# Mailbox_Notifier_2_1.net
KiCad netlist of a schematic drawn in EAGLE
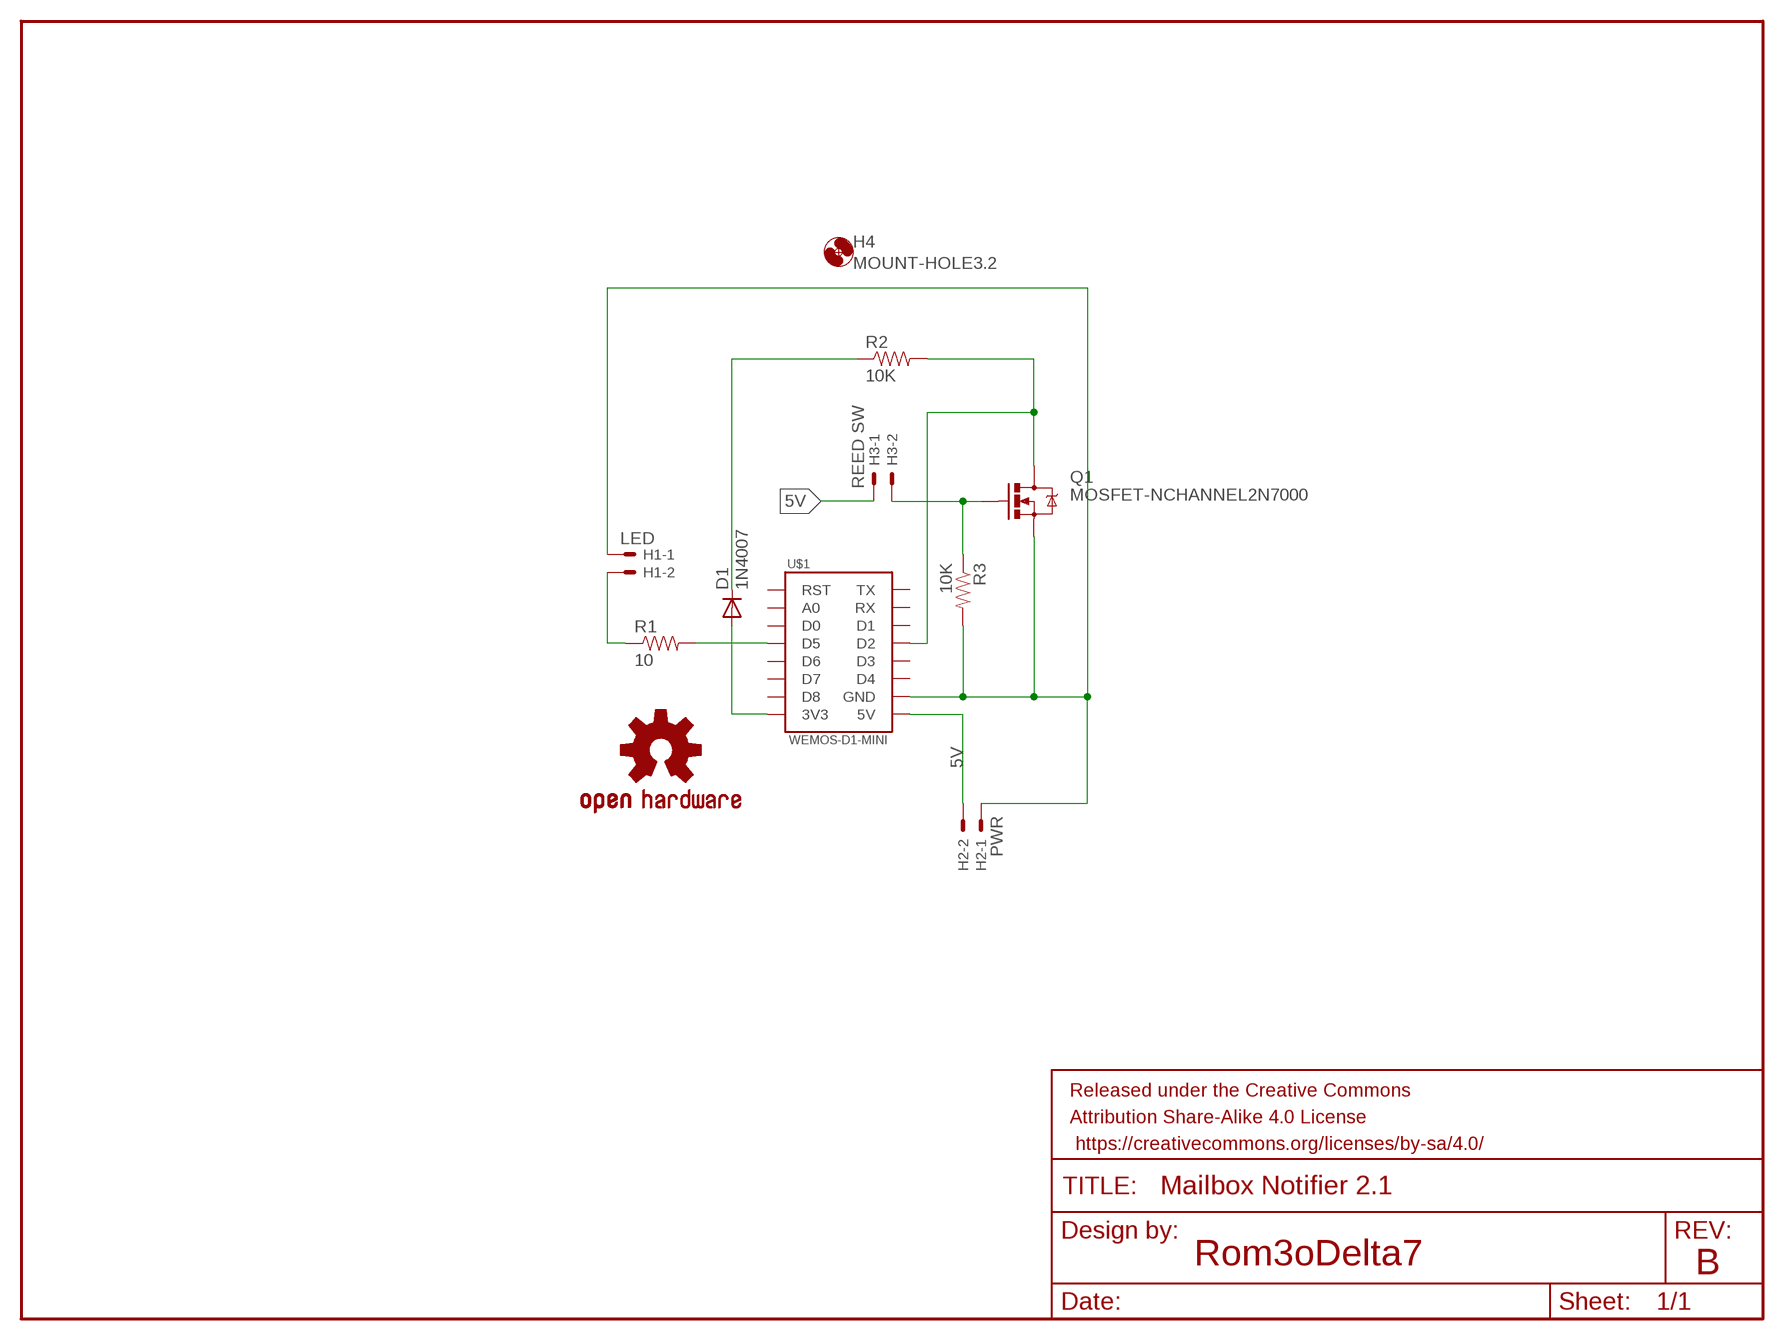
[diagram p0: schematic, sheet 1]

(export (version "E")
  (design (tool "Eeschema 10.0.6"))
  (components
    (comp (ref "D1")
      (value "1N4007")
      (footprint "eagle-import:DO41-10")
      (libsource (lib "eagle-import") (part "1N4004"))
    )
    (comp (ref "FRAME1")
      (value "FRAME-LETTER")
      (footprint "eagle-import:CREATIVE_COMMONS")
      (libsource (lib "eagle-import") (part "FRAME-LETTER"))
    )
    (comp (ref "H1")
      (value "LED")
      (footprint "eagle-import:22-23-2021")
      (fields (field (name "MF") "MOLEX") (field (name "MPN") "22-23-2021"))
      (libsource (lib "eagle-import") (part "22-23-2021"))
    )
    (comp (ref "H2")
      (value "PWR")
      (footprint "eagle-import:22-23-2021")
      (fields (field (name "MF") "MOLEX") (field (name "MPN") "22-23-2021"))
      (libsource (lib "eagle-import") (part "22-23-2021"))
    )
    (comp (ref "H3")
      (value "REED SW")
      (footprint "eagle-import:22-23-2021")
      (fields (field (name "MF") "MOLEX") (field (name "MPN") "22-23-2021"))
      (libsource (lib "eagle-import") (part "22-23-2021"))
    )
    (comp (ref "H4")
      (value "MOUNT-HOLE3.2")
      (footprint "eagle-import:3,2")
      (libsource (lib "eagle-import") (part "MOUNT-HOLE3.2"))
    )
    (comp (ref "LOGO1")
      (value "OSHW-LOGOMINI")
      (footprint "eagle-import:OSHW-LOGO-MINI")
      (libsource (lib "eagle-import") (part "OSHW-LOGOMINI"))
    )
    (comp (ref "Q1")
      (value "MOSFET-NCHANNEL2N7000")
      (footprint "eagle-import:TO-92")
      (libsource (lib "eagle-import") (part "MOSFET-NCHANNEL2N7000"))
    )
    (comp (ref "R1")
      (value "10")
      (footprint "eagle-import:AXIAL-0.5")
      (libsource (lib "eagle-import") (part "RESISTORPTH-1/2W"))
    )
    (comp (ref "R2")
      (value "10K")
      (footprint "eagle-import:AXIAL-0.4")
      (libsource (lib "eagle-import") (part "RESISTORPTH-1/4W"))
    )
    (comp (ref "R3")
      (value "10K")
      (footprint "eagle-import:AXIAL-0.4")
      (libsource (lib "eagle-import") (part "RESISTORPTH-1/4W"))
    )
    (comp (ref "U$1")
      (value "WEMOS-D1-MINI")
      (footprint "eagle-import:WEMOS-D1-MINI")
      (libsource (lib "eagle-import") (part "WEMOS-D1-MINI"))
    )
  )
  (nets
    (net (code "1") (name "5V") (class "Default")
      (node (ref "H2") (pin "2") (pinfunction "S_2") (pintype "passive"))
      (node (ref "H3") (pin "1") (pinfunction "S_1") (pintype "passive"))
      (node (ref "U$1") (pin "5V") (pinfunction "5V_5V") (pintype "power_in"))
    )
    (net (code "2") (name "Net-(D1-PadA)") (class "Default")
      (node (ref "D1") (pin "A") (pinfunction "A_A") (pintype "passive"))
      (node (ref "U$1") (pin "3V3") (pinfunction "3V3_3V3") (pintype "power_in"))
    )
    (net (code "3") (name "Net-(H1A-S)") (class "Default")
      (node (ref "H1") (pin "1") (pinfunction "S_1") (pintype "passive"))
      (node (ref "H2") (pin "1") (pinfunction "S_1") (pintype "passive"))
      (node (ref "Q1") (pin "1") (pinfunction "S_1") (pintype "passive"))
      (node (ref "R3") (pin "P$2") (pinfunction "2_P$2") (pintype "passive"))
      (node (ref "U$1") (pin "GND") (pinfunction "GND_GND") (pintype "power_in"))
    )
    (net (code "4") (name "Net-(H1B-S)") (class "Default")
      (node (ref "H1") (pin "2") (pinfunction "S_2") (pintype "passive"))
      (node (ref "R1") (pin "P$1") (pinfunction "1_P$1") (pintype "passive"))
    )
    (net (code "5") (name "Net-(H3B-S)") (class "Default")
      (node (ref "H3") (pin "2") (pinfunction "S_2") (pintype "passive"))
      (node (ref "Q1") (pin "2") (pinfunction "G_2") (pintype "passive"))
      (node (ref "R3") (pin "P$1") (pinfunction "1_P$1") (pintype "passive"))
    )
    (net (code "6") (name "Net-(Q1-D)") (class "Default")
      (node (ref "Q1") (pin "3") (pinfunction "D_3") (pintype "passive"))
      (node (ref "R2") (pin "P$2") (pinfunction "2_P$2") (pintype "passive"))
      (node (ref "U$1") (pin "D2") (pinfunction "D2_D2") (pintype "bidirectional"))
    )
    (net (code "7") (name "Net-(R1-2)") (class "Default")
      (node (ref "R1") (pin "P$2") (pinfunction "2_P$2") (pintype "passive"))
      (node (ref "U$1") (pin "D5") (pinfunction "D5_D5") (pintype "bidirectional"))
    )
    (net (code "8") (name "Net-(R2-1)") (class "Default")
      (node (ref "D1") (pin "C") (pinfunction "C_C") (pintype "passive"))
      (node (ref "R2") (pin "P$1") (pinfunction "1_P$1") (pintype "passive"))
    )
    (net (code "9") (name "unconnected-(U$1-PadA0)") (class "Default")
      (node (ref "U$1") (pin "A0") (pinfunction "A0_A0") (pintype "input"))
    )
    (net (code "10") (name "unconnected-(U$1-PadD0)") (class "Default")
      (node (ref "U$1") (pin "D0") (pinfunction "D0_D0") (pintype "bidirectional"))
    )
    (net (code "11") (name "unconnected-(U$1-PadD1)") (class "Default")
      (node (ref "U$1") (pin "D1") (pinfunction "D1_D1") (pintype "bidirectional"))
    )
    (net (code "12") (name "unconnected-(U$1-PadD3)") (class "Default")
      (node (ref "U$1") (pin "D3") (pinfunction "D3_D3") (pintype "bidirectional"))
    )
    (net (code "13") (name "unconnected-(U$1-PadD4)") (class "Default")
      (node (ref "U$1") (pin "D4") (pinfunction "D4_D4") (pintype "bidirectional"))
    )
    (net (code "14") (name "unconnected-(U$1-PadD6)") (class "Default")
      (node (ref "U$1") (pin "D6") (pinfunction "D6_D6") (pintype "bidirectional"))
    )
    (net (code "15") (name "unconnected-(U$1-PadD7)") (class "Default")
      (node (ref "U$1") (pin "D7") (pinfunction "D7_D7") (pintype "bidirectional"))
    )
    (net (code "16") (name "unconnected-(U$1-PadD8)") (class "Default")
      (node (ref "U$1") (pin "D8") (pinfunction "D8_D8") (pintype "bidirectional"))
    )
    (net (code "17") (name "unconnected-(U$1-PadRST)") (class "Default")
      (node (ref "U$1") (pin "RST") (pinfunction "RST_RST") (pintype "input"))
    )
    (net (code "18") (name "unconnected-(U$1-PadRX)") (class "Default")
      (node (ref "U$1") (pin "RX") (pinfunction "RX_RX") (pintype "input"))
    )
    (net (code "19") (name "unconnected-(U$1-PadTX)") (class "Default")
      (node (ref "U$1") (pin "TX") (pinfunction "TX_TX") (pintype "output"))
    )
  )
)
